# ZynqPL_GTXE2.net
KiCad netlist of a schematic drawn in Altium Designer
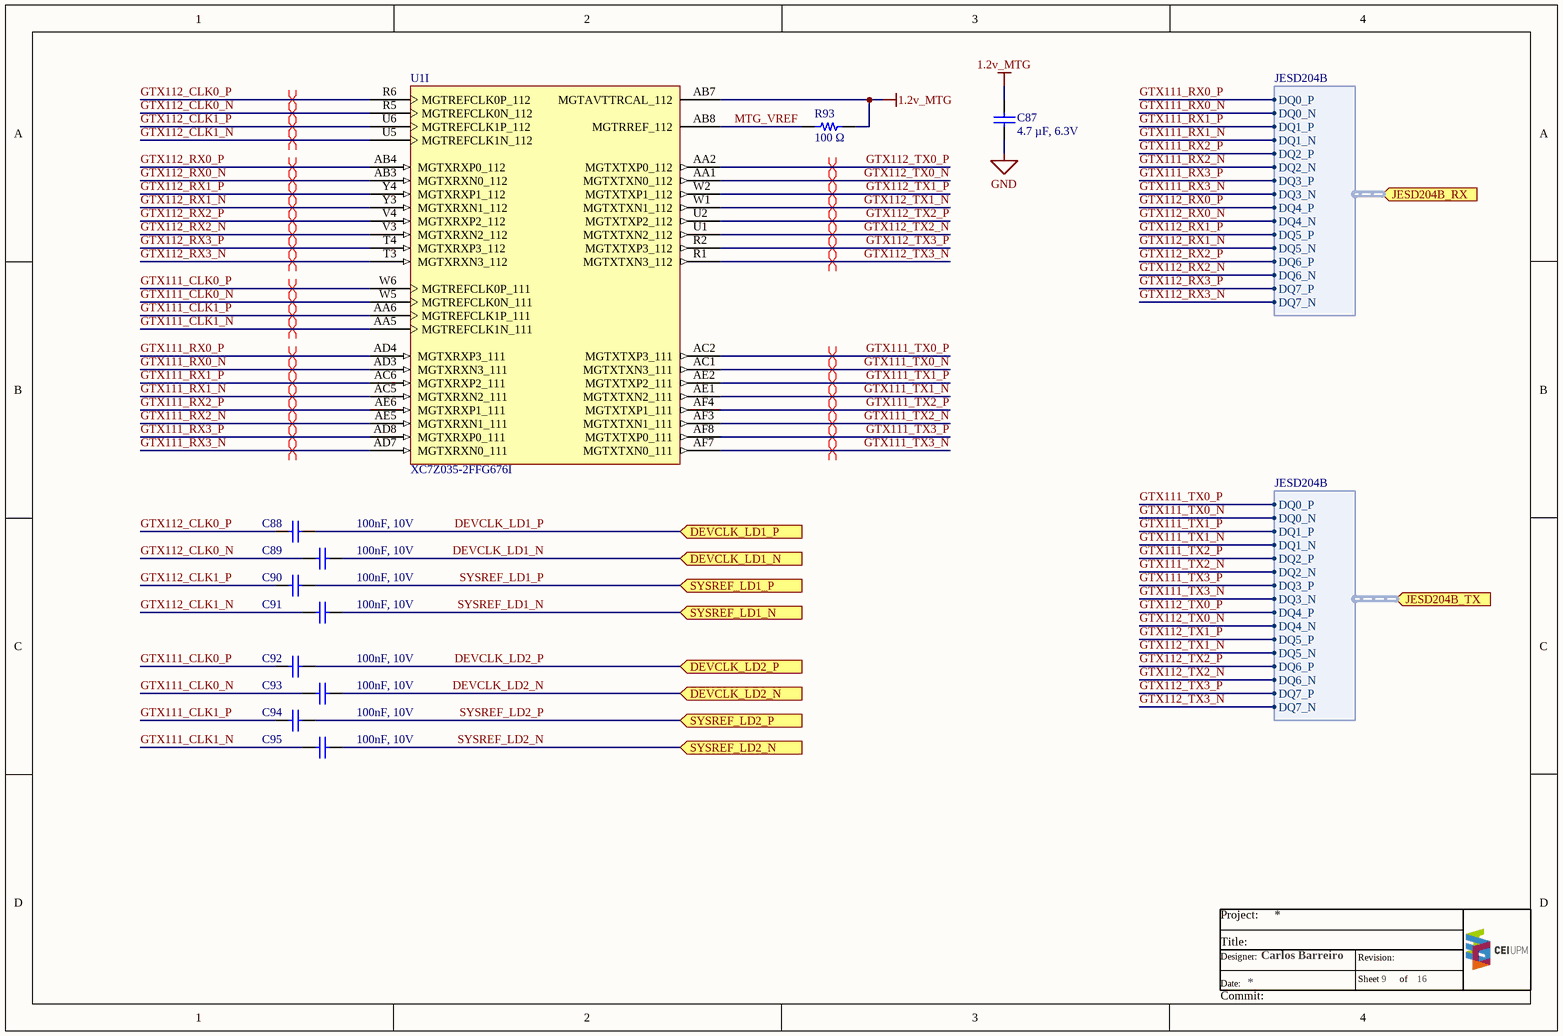
[diagram p0: ZynqPL_GTXE2.SchDoc]

(export (version "E")
  (design (tool "Eeschema 10.0.6"))
  (components
    (comp (ref "C87")
      (value "4.7 µF, 6.3V")
      (footprint "WURTH_WCAP-CSGP_0402")
      (description "Multilayer Ceramic Capacitors MLCC, size 0402, X5R, 4.7 µF, 6.3V")
      (fields
        (field (name "MANUFACTURER PART NUMBER") "GRM155C80J475MEAAD")
        (field (name "MANUFACTURER") "Murata")
      )
      (libsource (lib "SpaceVNXBaseBoard") (part "GRM155C80J475MEAAD"))
    )
    (comp (ref "C88")
      (value "100nF, 10V")
      (footprint "WURTH_WCAP-CSGP_0402")
      (description "WCAP-CSGP Multilayer Ceramic Chip Capacitor, General Purpose, size 0402, X7R, 100nF, 10V")
      (fields
        (field (name "MANUFACTURER PART NUMBER") "885012205018")
        (field (name "MANUFACTURER") "Wurth Elektronik")
      )
      (libsource (lib "SpaceVNXBaseBoard") (part "885012205018"))
    )
    (comp (ref "C89")
      (value "100nF, 10V")
      (footprint "WURTH_WCAP-CSGP_0402")
      (description "WCAP-CSGP Multilayer Ceramic Chip Capacitor, General Purpose, size 0402, X7R, 100nF, 10V")
      (fields
        (field (name "MANUFACTURER PART NUMBER") "885012205018")
        (field (name "MANUFACTURER") "Wurth Elektronik")
      )
      (libsource (lib "SpaceVNXBaseBoard") (part "885012205018"))
    )
    (comp (ref "C90")
      (value "100nF, 10V")
      (footprint "WURTH_WCAP-CSGP_0402")
      (description "WCAP-CSGP Multilayer Ceramic Chip Capacitor, General Purpose, size 0402, X7R, 100nF, 10V")
      (fields
        (field (name "MANUFACTURER PART NUMBER") "885012205018")
        (field (name "MANUFACTURER") "Wurth Elektronik")
      )
      (libsource (lib "SpaceVNXBaseBoard") (part "885012205018"))
    )
    (comp (ref "C91")
      (value "100nF, 10V")
      (footprint "WURTH_WCAP-CSGP_0402")
      (description "WCAP-CSGP Multilayer Ceramic Chip Capacitor, General Purpose, size 0402, X7R, 100nF, 10V")
      (fields
        (field (name "MANUFACTURER PART NUMBER") "885012205018")
        (field (name "MANUFACTURER") "Wurth Elektronik")
      )
      (libsource (lib "SpaceVNXBaseBoard") (part "885012205018"))
    )
    (comp (ref "C92")
      (value "100nF, 10V")
      (footprint "WURTH_WCAP-CSGP_0402")
      (description "WCAP-CSGP Multilayer Ceramic Chip Capacitor, General Purpose, size 0402, X7R, 100nF, 10V")
      (fields
        (field (name "MANUFACTURER PART NUMBER") "885012205018")
        (field (name "MANUFACTURER") "Wurth Elektronik")
      )
      (libsource (lib "SpaceVNXBaseBoard") (part "885012205018"))
    )
    (comp (ref "C93")
      (value "100nF, 10V")
      (footprint "WURTH_WCAP-CSGP_0402")
      (description "WCAP-CSGP Multilayer Ceramic Chip Capacitor, General Purpose, size 0402, X7R, 100nF, 10V")
      (fields
        (field (name "MANUFACTURER PART NUMBER") "885012205018")
        (field (name "MANUFACTURER") "Wurth Elektronik")
      )
      (libsource (lib "SpaceVNXBaseBoard") (part "885012205018"))
    )
    (comp (ref "C94")
      (value "100nF, 10V")
      (footprint "WURTH_WCAP-CSGP_0402")
      (description "WCAP-CSGP Multilayer Ceramic Chip Capacitor, General Purpose, size 0402, X7R, 100nF, 10V")
      (fields
        (field (name "MANUFACTURER PART NUMBER") "885012205018")
        (field (name "MANUFACTURER") "Wurth Elektronik")
      )
      (libsource (lib "SpaceVNXBaseBoard") (part "885012205018"))
    )
    (comp (ref "C95")
      (value "100nF, 10V")
      (footprint "WURTH_WCAP-CSGP_0402")
      (description "WCAP-CSGP Multilayer Ceramic Chip Capacitor, General Purpose, size 0402, X7R, 100nF, 10V")
      (fields
        (field (name "MANUFACTURER PART NUMBER") "885012205018")
        (field (name "MANUFACTURER") "Wurth Elektronik")
      )
      (libsource (lib "SpaceVNXBaseBoard") (part "885012205018"))
    )
    (comp (ref "R93")
      (value "100 Ω")
      (footprint "PANASONIC_ERJ2G_0402")
      (description "General Purpose Thick Film Chip Resistors")
      (fields (field (name "MANUFACTURER") "Panasonic"))
      (libsource (lib "SpaceVNXBaseBoard") (part "ERJ2GEJ101X"))
    )
    (comp (ref "U1")
      (value "XC7Z035-2FFG676I")
      (footprint "XILINX_FBG676")
      (fields (field (name "PARTNUMBER") "XC7Z035-2FBG676I") (field (name "GENERIC PART NUMBER") "XC7Z035"))
      (libsource (lib "SpaceVNXBaseBoard") (part "XC7Z035-2FFG676I"))
    )
  )
  (nets
    (net (code "2") (name "/DEVCLK_LD1_N") (class "Default")
      (node (ref "C89") (pin "2") (pinfunction "2_2") (pintype "passive"))
    )
    (net (code "3") (name "/DEVCLK_LD1_P") (class "Default")
      (node (ref "C88") (pin "2") (pinfunction "2_2") (pintype "passive"))
    )
    (net (code "4") (name "/DEVCLK_LD2_N") (class "Default")
      (node (ref "C93") (pin "2") (pinfunction "2_2") (pintype "passive"))
    )
    (net (code "5") (name "/DEVCLK_LD2_P") (class "Default")
      (node (ref "C92") (pin "2") (pinfunction "2_2") (pintype "passive"))
    )
    (net (code "6") (name "/GTX111_CLK0_N") (class "Default")
      (node (ref "C93") (pin "1") (pinfunction "1_1") (pintype "passive"))
      (node (ref "U1") (pin "W5") (pinfunction "MGTREFCLK0N_111_W5") (pintype "passive"))
    )
    (net (code "7") (name "/GTX111_CLK0_P") (class "Default")
      (node (ref "C92") (pin "1") (pinfunction "1_1") (pintype "passive"))
      (node (ref "U1") (pin "W6") (pinfunction "MGTREFCLK0P_111_W6") (pintype "passive"))
    )
    (net (code "8") (name "/GTX111_CLK1_N") (class "Default")
      (node (ref "C95") (pin "1") (pinfunction "1_1") (pintype "passive"))
      (node (ref "U1") (pin "AA5") (pinfunction "MGTREFCLK1N_111_AA5") (pintype "passive"))
    )
    (net (code "9") (name "/GTX111_CLK1_P") (class "Default")
      (node (ref "C94") (pin "1") (pinfunction "1_1") (pintype "passive"))
      (node (ref "U1") (pin "AA6") (pinfunction "MGTREFCLK1P_111_AA6") (pintype "passive"))
    )
    (net (code "10") (name "/GTX111_RX0_N") (class "Default")
      (node (ref "U1") (pin "AD3") (pinfunction "MGTXRXN3_111_AD3") (pintype "input"))
    )
    (net (code "11") (name "/GTX111_RX0_P") (class "Default")
      (node (ref "U1") (pin "AD4") (pinfunction "MGTXRXP3_111_AD4") (pintype "input"))
    )
    (net (code "12") (name "/GTX111_RX1_N") (class "Default")
      (node (ref "U1") (pin "AC5") (pinfunction "MGTXRXN2_111_AC5") (pintype "input"))
    )
    (net (code "13") (name "/GTX111_RX1_P") (class "Default")
      (node (ref "U1") (pin "AC6") (pinfunction "MGTXRXP2_111_AC6") (pintype "input"))
    )
    (net (code "14") (name "/GTX111_RX2_N") (class "Default")
      (node (ref "U1") (pin "AE5") (pinfunction "MGTXRXN1_111_AE5") (pintype "input"))
    )
    (net (code "15") (name "/GTX111_RX2_P") (class "Default")
      (node (ref "U1") (pin "AE6") (pinfunction "MGTXRXP1_111_AE6") (pintype "input"))
    )
    (net (code "16") (name "/GTX111_RX3_N") (class "Default")
      (node (ref "U1") (pin "AD7") (pinfunction "MGTXRXN0_111_AD7") (pintype "input"))
    )
    (net (code "17") (name "/GTX111_RX3_P") (class "Default")
      (node (ref "U1") (pin "AD8") (pinfunction "MGTXRXP0_111_AD8") (pintype "input"))
    )
    (net (code "18") (name "/GTX111_TX0_N") (class "Default")
      (node (ref "U1") (pin "AC1") (pinfunction "MGTXTXN3_111_AC1") (pintype "output"))
    )
    (net (code "19") (name "/GTX111_TX0_P") (class "Default")
      (node (ref "U1") (pin "AC2") (pinfunction "MGTXTXP3_111_AC2") (pintype "output"))
    )
    (net (code "20") (name "/GTX111_TX1_N") (class "Default")
      (node (ref "U1") (pin "AE1") (pinfunction "MGTXTXN2_111_AE1") (pintype "output"))
    )
    (net (code "21") (name "/GTX111_TX1_P") (class "Default")
      (node (ref "U1") (pin "AE2") (pinfunction "MGTXTXP2_111_AE2") (pintype "output"))
    )
    (net (code "22") (name "/GTX111_TX2_N") (class "Default")
      (node (ref "U1") (pin "AF3") (pinfunction "MGTXTXN1_111_AF3") (pintype "output"))
    )
    (net (code "23") (name "/GTX111_TX2_P") (class "Default")
      (node (ref "U1") (pin "AF4") (pinfunction "MGTXTXP1_111_AF4") (pintype "output"))
    )
    (net (code "24") (name "/GTX111_TX3_N") (class "Default")
      (node (ref "U1") (pin "AF7") (pinfunction "MGTXTXN0_111_AF7") (pintype "output"))
    )
    (net (code "25") (name "/GTX111_TX3_P") (class "Default")
      (node (ref "U1") (pin "AF8") (pinfunction "MGTXTXP0_111_AF8") (pintype "output"))
    )
    (net (code "26") (name "/GTX112_CLK0_N") (class "Default")
      (node (ref "C89") (pin "1") (pinfunction "1_1") (pintype "passive"))
      (node (ref "U1") (pin "R5") (pinfunction "MGTREFCLK0N_112_R5") (pintype "passive"))
    )
    (net (code "27") (name "/GTX112_CLK0_P") (class "Default")
      (node (ref "C88") (pin "1") (pinfunction "1_1") (pintype "passive"))
      (node (ref "U1") (pin "R6") (pinfunction "MGTREFCLK0P_112_R6") (pintype "passive"))
    )
    (net (code "28") (name "/GTX112_CLK1_N") (class "Default")
      (node (ref "C91") (pin "1") (pinfunction "1_1") (pintype "passive"))
      (node (ref "U1") (pin "U5") (pinfunction "MGTREFCLK1N_112_U5") (pintype "passive"))
    )
    (net (code "29") (name "/GTX112_CLK1_P") (class "Default")
      (node (ref "C90") (pin "1") (pinfunction "1_1") (pintype "passive"))
      (node (ref "U1") (pin "U6") (pinfunction "MGTREFCLK1P_112_U6") (pintype "passive"))
    )
    (net (code "30") (name "/GTX112_RX0_N") (class "Default")
      (node (ref "U1") (pin "AB3") (pinfunction "MGTXRXN0_112_AB3") (pintype "input"))
    )
    (net (code "31") (name "/GTX112_RX0_P") (class "Default")
      (node (ref "U1") (pin "AB4") (pinfunction "MGTXRXP0_112_AB4") (pintype "input"))
    )
    (net (code "32") (name "/GTX112_RX1_N") (class "Default")
      (node (ref "U1") (pin "Y3") (pinfunction "MGTXRXN1_112_Y3") (pintype "input"))
    )
    (net (code "33") (name "/GTX112_RX1_P") (class "Default")
      (node (ref "U1") (pin "Y4") (pinfunction "MGTXRXP1_112_Y4") (pintype "input"))
    )
    (net (code "34") (name "/GTX112_RX2_N") (class "Default")
      (node (ref "U1") (pin "V3") (pinfunction "MGTXRXN2_112_V3") (pintype "input"))
    )
    (net (code "35") (name "/GTX112_RX2_P") (class "Default")
      (node (ref "U1") (pin "V4") (pinfunction "MGTXRXP2_112_V4") (pintype "input"))
    )
    (net (code "36") (name "/GTX112_RX3_N") (class "Default")
      (node (ref "U1") (pin "T3") (pinfunction "MGTXRXN3_112_T3") (pintype "input"))
    )
    (net (code "37") (name "/GTX112_RX3_P") (class "Default")
      (node (ref "U1") (pin "T4") (pinfunction "MGTXRXP3_112_T4") (pintype "input"))
    )
    (net (code "38") (name "/GTX112_TX0_N") (class "Default")
      (node (ref "U1") (pin "AA1") (pinfunction "MGTXTXN0_112_AA1") (pintype "output"))
    )
    (net (code "39") (name "/GTX112_TX0_P") (class "Default")
      (node (ref "U1") (pin "AA2") (pinfunction "MGTXTXP0_112_AA2") (pintype "output"))
    )
    (net (code "40") (name "/GTX112_TX1_N") (class "Default")
      (node (ref "U1") (pin "W1") (pinfunction "MGTXTXN1_112_W1") (pintype "output"))
    )
    (net (code "41") (name "/GTX112_TX1_P") (class "Default")
      (node (ref "U1") (pin "W2") (pinfunction "MGTXTXP1_112_W2") (pintype "output"))
    )
    (net (code "42") (name "/GTX112_TX2_N") (class "Default")
      (node (ref "U1") (pin "U1") (pinfunction "MGTXTXN2_112_U1") (pintype "output"))
    )
    (net (code "43") (name "/GTX112_TX2_P") (class "Default")
      (node (ref "U1") (pin "U2") (pinfunction "MGTXTXP2_112_U2") (pintype "output"))
    )
    (net (code "44") (name "/GTX112_TX3_N") (class "Default")
      (node (ref "U1") (pin "R1") (pinfunction "MGTXTXN3_112_R1") (pintype "output"))
    )
    (net (code "45") (name "/GTX112_TX3_P") (class "Default")
      (node (ref "U1") (pin "R2") (pinfunction "MGTXTXP3_112_R2") (pintype "output"))
    )
    (net (code "46") (name "/MTG_VREF") (class "Default")
      (node (ref "R93") (pin "1") (pinfunction "1_1") (pintype "passive"))
      (node (ref "U1") (pin "AB8") (pinfunction "MGTRREF_112_AB8") (pintype "passive"))
    )
    (net (code "47") (name "/SYSREF_LD1_N") (class "Default")
      (node (ref "C91") (pin "2") (pinfunction "2_2") (pintype "passive"))
    )
    (net (code "48") (name "/SYSREF_LD1_P") (class "Default")
      (node (ref "C90") (pin "2") (pinfunction "2_2") (pintype "passive"))
    )
    (net (code "49") (name "/SYSREF_LD2_N") (class "Default")
      (node (ref "C95") (pin "2") (pinfunction "2_2") (pintype "passive"))
    )
    (net (code "50") (name "/SYSREF_LD2_P") (class "Default")
      (node (ref "C94") (pin "2") (pinfunction "2_2") (pintype "passive"))
    )
    (net (code "52") (name "1.2v_MTG") (class "Default")
      (node (ref "C87") (pin "2") (pinfunction "2_2") (pintype "passive"))
      (node (ref "R93") (pin "2") (pinfunction "2_2") (pintype "passive"))
      (node (ref "U1") (pin "AB7") (pinfunction "MGTAVTTRCAL_112_AB7") (pintype "passive"))
    )
    (net (code "53") (name "GND") (class "Default")
      (node (ref "C87") (pin "1") (pinfunction "1_1") (pintype "passive"))
    )
  )
)
